# TSOC_GROVEY_ADC.net
KiCad netlist of a schematic drawn in EAGLE
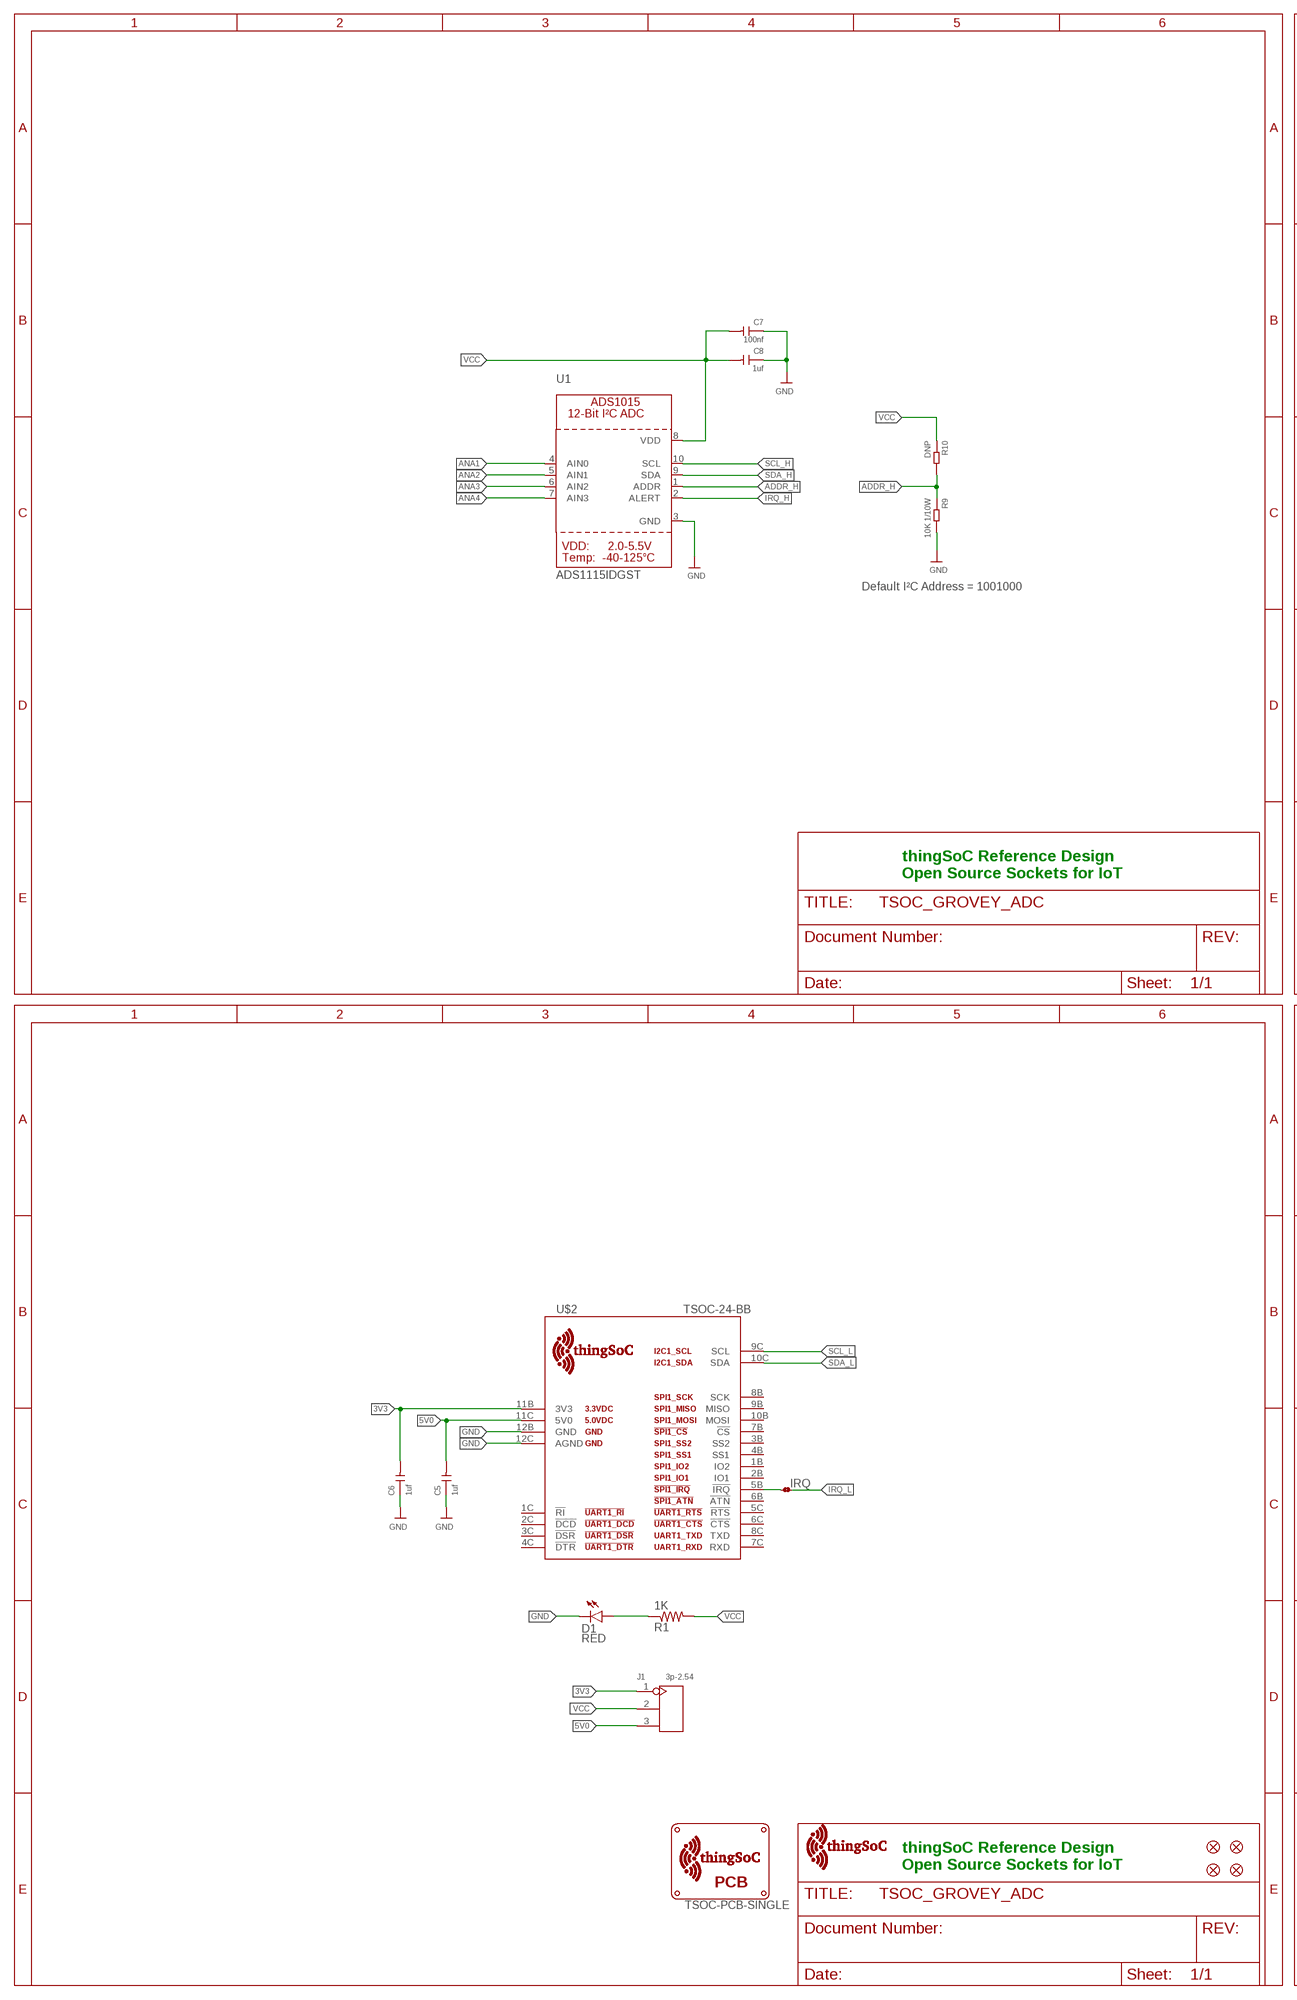
[diagram p0: schematic, sheet 1, part 1 of 2]
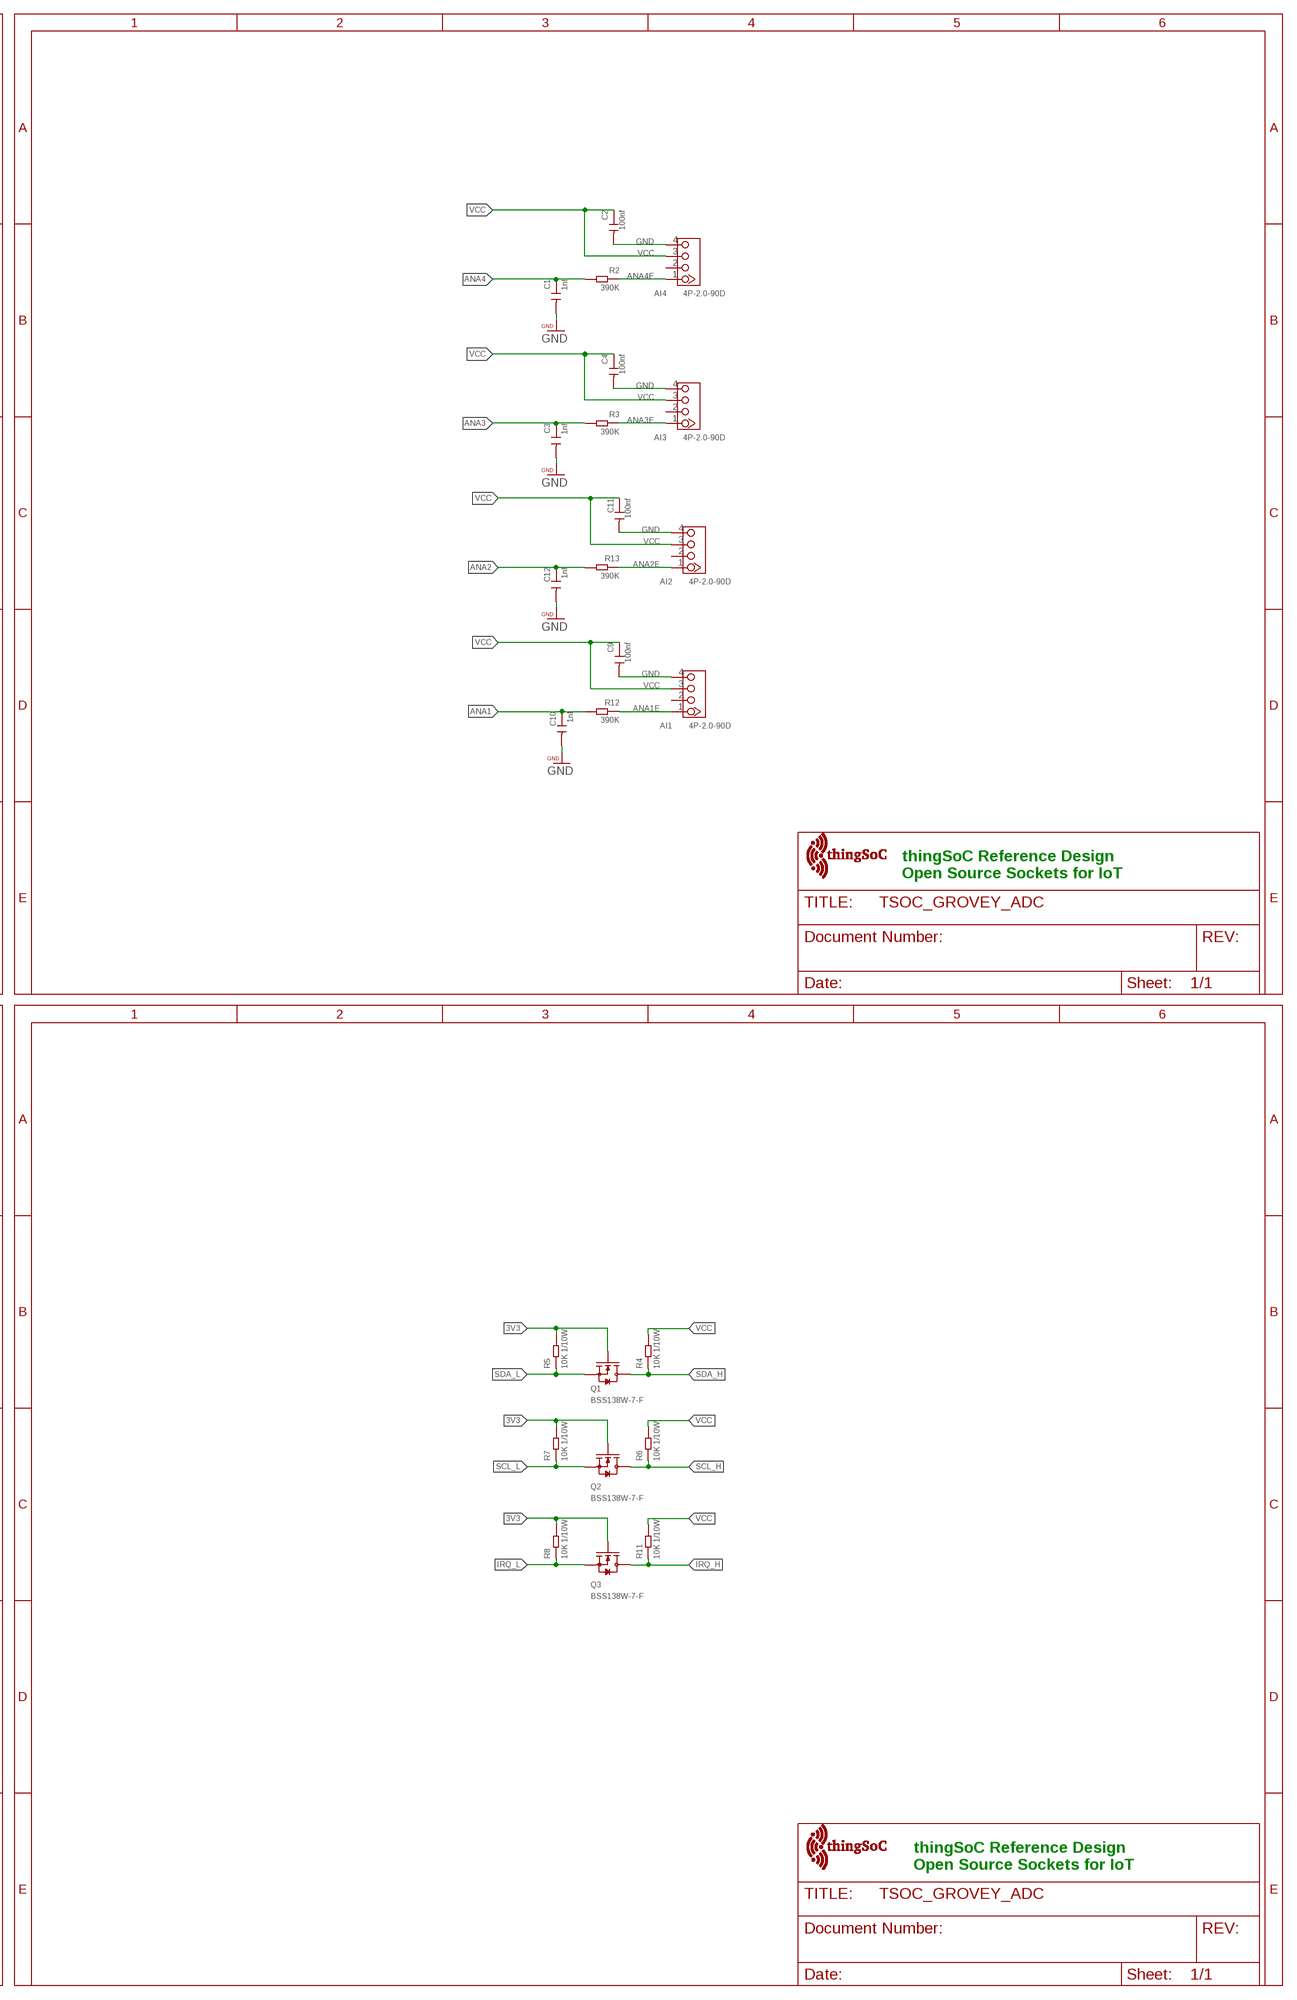
[diagram p1: schematic, sheet 1, part 2 of 2]

(export (version "E")
  (design (tool "Eeschema 10.0.6"))
  (components
    (comp (ref "AI1")
      (value "4P-2.0-90D")
      (footprint "eagle-import:HW4-2.0-90D")
      (libsource (lib "eagle-import") (part "GROVE-CONNECTOR-DIP-90D(4P-2.0)"))
    )
    (comp (ref "AI2")
      (value "4P-2.0-90D")
      (footprint "eagle-import:HW4-2.0-90D")
      (libsource (lib "eagle-import") (part "GROVE-CONNECTOR-DIP-90D(4P-2.0)"))
    )
    (comp (ref "AI3")
      (value "4P-2.0-90D")
      (footprint "eagle-import:HW4-2.0-90D")
      (libsource (lib "eagle-import") (part "GROVE-CONNECTOR-DIP-90D(4P-2.0)"))
    )
    (comp (ref "AI4")
      (value "4P-2.0-90D")
      (footprint "eagle-import:HW4-2.0-90D")
      (libsource (lib "eagle-import") (part "GROVE-CONNECTOR-DIP-90D(4P-2.0)"))
    )
    (comp (ref "C1")
      (value "1nf")
      (footprint "eagle-import:C0603")
      (fields (field (name "MPN") "GRM1885C1H102JA01D"))
      (libsource (lib "eagle-import") (part "CERAMIC-1NF-50V-5%-C0G(0603)"))
    )
    (comp (ref "C2")
      (value "100nf")
      (footprint "eagle-import:C0603")
      (fields (field (name "MPN") "CC0603KRX7R9BB104"))
      (libsource (lib "eagle-import") (part "CERAMIC-100NF-50V-10%-X7R(0603)"))
    )
    (comp (ref "C3")
      (value "1nf")
      (footprint "eagle-import:C0603")
      (fields (field (name "MPN") "GRM1885C1H102JA01D"))
      (libsource (lib "eagle-import") (part "CERAMIC-1NF-50V-5%-C0G(0603)"))
    )
    (comp (ref "C4")
      (value "100nf")
      (footprint "eagle-import:C0603")
      (fields (field (name "MPN") "CC0603KRX7R9BB104"))
      (libsource (lib "eagle-import") (part "CERAMIC-100NF-50V-10%-X7R(0603)"))
    )
    (comp (ref "C5")
      (value "1uf")
      (footprint "eagle-import:C0603")
      (fields (field (name "MPN") "CC0603KRX7R8BB105"))
      (libsource (lib "eagle-import") (part "CERAMIC-1UF-25V-10%-X7R(0603)"))
    )
    (comp (ref "C6")
      (value "1uf")
      (footprint "eagle-import:C0603")
      (fields (field (name "MPN") "CC0603KRX7R8BB105"))
      (libsource (lib "eagle-import") (part "CERAMIC-1UF-25V-10%-X7R(0603)"))
    )
    (comp (ref "C7")
      (value "100nf")
      (footprint "eagle-import:C0603")
      (fields (field (name "MPN") "CC0603KRX7R9BB104"))
      (libsource (lib "eagle-import") (part "CERAMIC-100NF-50V-10%-X7R(0603)"))
    )
    (comp (ref "C8")
      (value "1uf")
      (footprint "eagle-import:C0603")
      (fields (field (name "MPN") "CC0603KRX7R8BB105"))
      (libsource (lib "eagle-import") (part "CERAMIC-1UF-25V-10%-X7R(0603)"))
    )
    (comp (ref "C9")
      (value "100nf")
      (footprint "eagle-import:C0603")
      (fields (field (name "MPN") "CC0603KRX7R9BB104"))
      (libsource (lib "eagle-import") (part "CERAMIC-100NF-50V-10%-X7R(0603)"))
    )
    (comp (ref "C10")
      (value "1nf")
      (footprint "eagle-import:C0603")
      (fields (field (name "MPN") "GRM1885C1H102JA01D"))
      (libsource (lib "eagle-import") (part "CERAMIC-1NF-50V-5%-C0G(0603)"))
    )
    (comp (ref "C11")
      (value "100nf")
      (footprint "eagle-import:C0603")
      (fields (field (name "MPN") "CC0603KRX7R9BB104"))
      (libsource (lib "eagle-import") (part "CERAMIC-100NF-50V-10%-X7R(0603)"))
    )
    (comp (ref "C12")
      (value "1nf")
      (footprint "eagle-import:C0603")
      (fields (field (name "MPN") "GRM1885C1H102JA01D"))
      (libsource (lib "eagle-import") (part "CERAMIC-1NF-50V-5%-C0G(0603)"))
    )
    (comp (ref "D1")
      (value "RED")
      (footprint "eagle-import:LED-0603")
      (libsource (lib "eagle-import") (part "LED0603"))
    )
    (comp (ref "FID1")
      (value "FIDUCIALUFIDUCIAL")
      (footprint "eagle-import:MICRO-FIDUCIAL")
      (libsource (lib "eagle-import") (part "FIDUCIALUFIDUCIAL"))
    )
    (comp (ref "FID2")
      (value "FIDUCIALUFIDUCIAL")
      (footprint "eagle-import:MICRO-FIDUCIAL")
      (libsource (lib "eagle-import") (part "FIDUCIALUFIDUCIAL"))
    )
    (comp (ref "FID3")
      (value "FIDUCIALUFIDUCIAL")
      (footprint "eagle-import:MICRO-FIDUCIAL")
      (libsource (lib "eagle-import") (part "FIDUCIALUFIDUCIAL"))
    )
    (comp (ref "FID4")
      (value "FIDUCIALUFIDUCIAL")
      (footprint "eagle-import:MICRO-FIDUCIAL")
      (libsource (lib "eagle-import") (part "FIDUCIALUFIDUCIAL"))
    )
    (comp (ref "IRQ")
      (value "JMP-2-NO")
      (footprint "eagle-import:JMP-2-NO")
      (libsource (lib "eagle-import") (part "JMP-2-NO"))
    )
    (comp (ref "J1")
      (value "3p-2.54")
      (footprint "eagle-import:H3-2.54")
      (libsource (lib "eagle-import") (part "DIP-BLACK-MALE-HEADER-VERT(3P-2.54)"))
    )
    (comp (ref "Q1")
      (value "BSS138W-7-F")
      (footprint "eagle-import:SOT-23")
      (libsource (lib "eagle-import") (part "SMD-MOSFET-N-CH-50V-200MA-BSS138W-7-F(SOT-23)"))
    )
    (comp (ref "Q2")
      (value "BSS138W-7-F")
      (footprint "eagle-import:SOT-23")
      (libsource (lib "eagle-import") (part "SMD-MOSFET-N-CH-50V-200MA-BSS138W-7-F(SOT-23)"))
    )
    (comp (ref "Q3")
      (value "BSS138W-7-F")
      (footprint "eagle-import:SOT-23")
      (libsource (lib "eagle-import") (part "SMD-MOSFET-N-CH-50V-200MA-BSS138W-7-F(SOT-23)"))
    )
    (comp (ref "R1")
      (value "1K")
      (footprint "eagle-import:0603-RES")
      (libsource (lib "eagle-import") (part "RESISTOR_SFE0603-RES"))
    )
    (comp (ref "R2")
      (value "390K")
      (footprint "eagle-import:R0603")
      (fields (field (name "MPN") "RC0603FR-07150KL"))
      (libsource (lib "eagle-import") (part "SMD-RES-150K-1%-1/10W(0603)"))
    )
    (comp (ref "R3")
      (value "390K")
      (footprint "eagle-import:R0603")
      (fields (field (name "MPN") "RC0603FR-07150KL"))
      (libsource (lib "eagle-import") (part "SMD-RES-150K-1%-1/10W(0603)"))
    )
    (comp (ref "R4")
      (value "10K 1/10W")
      (footprint "eagle-import:R0603")
      (fields (field (name "MPN") "RC0603JR-0710KL"))
      (libsource (lib "eagle-import") (part "SMD-RES-10K-5%-1/10W(0603)"))
    )
    (comp (ref "R5")
      (value "10K 1/10W")
      (footprint "eagle-import:R0603")
      (fields (field (name "MPN") "RC0603JR-0710KL"))
      (libsource (lib "eagle-import") (part "SMD-RES-10K-5%-1/10W(0603)"))
    )
    (comp (ref "R6")
      (value "10K 1/10W")
      (footprint "eagle-import:R0603")
      (fields (field (name "MPN") "RC0603JR-0710KL"))
      (libsource (lib "eagle-import") (part "SMD-RES-10K-5%-1/10W(0603)"))
    )
    (comp (ref "R7")
      (value "10K 1/10W")
      (footprint "eagle-import:R0603")
      (fields (field (name "MPN") "RC0603JR-0710KL"))
      (libsource (lib "eagle-import") (part "SMD-RES-10K-5%-1/10W(0603)"))
    )
    (comp (ref "R8")
      (value "10K 1/10W")
      (footprint "eagle-import:R0603")
      (fields (field (name "MPN") "RC0603JR-0710KL"))
      (libsource (lib "eagle-import") (part "SMD-RES-10K-5%-1/10W(0603)"))
    )
    (comp (ref "R9")
      (value "10K 1/10W")
      (footprint "eagle-import:R0603")
      (fields (field (name "MPN") "RC0603JR-0710KL"))
      (libsource (lib "eagle-import") (part "SMD-RES-10K-5%-1/10W(0603)"))
    )
    (comp (ref "R10")
      (value "DNP")
      (footprint "eagle-import:R0603")
      (fields (field (name "MPN") "RC0603JR-0710KL"))
      (libsource (lib "eagle-import") (part "SMD-RES-10K-5%-1/10W(0603)"))
    )
    (comp (ref "R11")
      (value "10K 1/10W")
      (footprint "eagle-import:R0603")
      (fields (field (name "MPN") "RC0603JR-0710KL"))
      (libsource (lib "eagle-import") (part "SMD-RES-10K-5%-1/10W(0603)"))
    )
    (comp (ref "R12")
      (value "390K")
      (footprint "eagle-import:R0603")
      (fields (field (name "MPN") "RC0603FR-07150KL"))
      (libsource (lib "eagle-import") (part "SMD-RES-150K-1%-1/10W(0603)"))
    )
    (comp (ref "R13")
      (value "390K")
      (footprint "eagle-import:R0603")
      (fields (field (name "MPN") "RC0603FR-07150KL"))
      (libsource (lib "eagle-import") (part "SMD-RES-150K-1%-1/10W(0603)"))
    )
    (comp (ref "U$1")
      (value "TSOC-PCB-SINGLE")
      (footprint "eagle-import:TSOC-BB-BRD-DIM")
      (libsource (lib "eagle-import") (part "TSOC-PCB-SINGLE"))
    )
    (comp (ref "U$2")
      (value "TSOC-24-BB")
      (footprint "eagle-import:TSOC-BB-S24")
      (libsource (lib "eagle-import") (part "TSOC-24-BB"))
    )
    (comp (ref "U$100")
      (value "TSOC-LOGO-SMALL")
      (footprint "eagle-import:TSOC-LOGO-SML")
      (libsource (lib "eagle-import") (part "TSOC-LOGO-SMALL"))
    )
    (comp (ref "U$102")
      (value "TSOC-LOGO-LRG")
      (footprint "eagle-import:TSOC-LOGO-LRG")
      (libsource (lib "eagle-import") (part "TSOC-LOGO-LRG"))
    )
    (comp (ref "U$103")
      (value "TSOC-LOGO-SMALL")
      (footprint "eagle-import:TSOC-LOGO-SML")
      (libsource (lib "eagle-import") (part "TSOC-LOGO-SMALL"))
    )
    (comp (ref "U1")
      (value "ADS1115IDGST")
      (footprint "eagle-import:MSOP10")
      (libsource (lib "eagle-import") (part "ADC_ADS1015"))
    )
  )
  (nets
    (net (code "1") (name "/ANA1E") (class "Default")
      (node (ref "AI1") (pin "1") (pinfunction "1_1") (pintype "bidirectional"))
      (node (ref "R12") (pin "1") (pinfunction "1_1") (pintype "passive"))
    )
    (net (code "2") (name "/ANA2E") (class "Default")
      (node (ref "AI2") (pin "1") (pinfunction "1_1") (pintype "bidirectional"))
      (node (ref "R13") (pin "1") (pinfunction "1_1") (pintype "passive"))
    )
    (net (code "3") (name "/ANA3E") (class "Default")
      (node (ref "AI3") (pin "1") (pinfunction "1_1") (pintype "bidirectional"))
      (node (ref "R3") (pin "1") (pinfunction "1_1") (pintype "passive"))
    )
    (net (code "4") (name "/ANA4E") (class "Default")
      (node (ref "AI4") (pin "1") (pinfunction "1_1") (pintype "bidirectional"))
      (node (ref "R2") (pin "1") (pinfunction "1_1") (pintype "passive"))
    )
    (net (code "5") (name "3V3") (class "Default")
      (node (ref "C6") (pin "2") (pinfunction "2_2") (pintype "passive"))
      (node (ref "J1") (pin "1") (pinfunction "P$1_1") (pintype "bidirectional"))
      (node (ref "Q1") (pin "1") (pinfunction "G_1") (pintype "passive"))
      (node (ref "Q2") (pin "1") (pinfunction "G_1") (pintype "passive"))
      (node (ref "Q3") (pin "1") (pinfunction "G_1") (pintype "passive"))
      (node (ref "R5") (pin "2") (pinfunction "2_2") (pintype "passive"))
      (node (ref "R7") (pin "2") (pinfunction "2_2") (pintype "passive"))
      (node (ref "R8") (pin "2") (pinfunction "2_2") (pintype "passive"))
      (node (ref "U$2") (pin "11B") (pinfunction "3V3_11B") (pintype "bidirectional"))
    )
    (net (code "6") (name "5V0") (class "Default")
      (node (ref "C5") (pin "2") (pinfunction "2_2") (pintype "passive"))
      (node (ref "J1") (pin "3") (pinfunction "P$3_3") (pintype "bidirectional"))
      (node (ref "U$2") (pin "11C") (pinfunction "5V0_11C") (pintype "bidirectional"))
    )
    (net (code "7") (name "ADDR_H") (class "Default")
      (node (ref "R10") (pin "2") (pinfunction "2_2") (pintype "passive"))
      (node (ref "R9") (pin "1") (pinfunction "1_1") (pintype "passive"))
      (node (ref "U1") (pin "1") (pinfunction "ADDR_1") (pintype "bidirectional"))
    )
    (net (code "8") (name "ANA1") (class "Default")
      (node (ref "C10") (pin "1") (pinfunction "1_1") (pintype "passive"))
      (node (ref "R12") (pin "2") (pinfunction "2_2") (pintype "passive"))
      (node (ref "U1") (pin "4") (pinfunction "AIN0_4") (pintype "bidirectional"))
    )
    (net (code "9") (name "ANA2") (class "Default")
      (node (ref "C12") (pin "1") (pinfunction "1_1") (pintype "passive"))
      (node (ref "R13") (pin "2") (pinfunction "2_2") (pintype "passive"))
      (node (ref "U1") (pin "5") (pinfunction "AIN1_5") (pintype "bidirectional"))
    )
    (net (code "10") (name "ANA3") (class "Default")
      (node (ref "C3") (pin "1") (pinfunction "1_1") (pintype "passive"))
      (node (ref "R3") (pin "2") (pinfunction "2_2") (pintype "passive"))
      (node (ref "U1") (pin "6") (pinfunction "AIN2_6") (pintype "bidirectional"))
    )
    (net (code "11") (name "ANA4") (class "Default")
      (node (ref "C1") (pin "1") (pinfunction "1_1") (pintype "passive"))
      (node (ref "R2") (pin "2") (pinfunction "2_2") (pintype "passive"))
      (node (ref "U1") (pin "7") (pinfunction "AIN3_7") (pintype "bidirectional"))
    )
    (net (code "12") (name "GND") (class "Default")
      (node (ref "AI1") (pin "4") (pinfunction "4_4") (pintype "bidirectional"))
      (node (ref "AI2") (pin "4") (pinfunction "4_4") (pintype "bidirectional"))
      (node (ref "AI3") (pin "4") (pinfunction "4_4") (pintype "bidirectional"))
      (node (ref "AI4") (pin "4") (pinfunction "4_4") (pintype "bidirectional"))
      (node (ref "C1") (pin "2") (pinfunction "2_2") (pintype "passive"))
      (node (ref "C10") (pin "2") (pinfunction "2_2") (pintype "passive"))
      (node (ref "C11") (pin "2") (pinfunction "2_2") (pintype "passive"))
      (node (ref "C12") (pin "2") (pinfunction "2_2") (pintype "passive"))
      (node (ref "C2") (pin "2") (pinfunction "2_2") (pintype "passive"))
      (node (ref "C3") (pin "2") (pinfunction "2_2") (pintype "passive"))
      (node (ref "C4") (pin "2") (pinfunction "2_2") (pintype "passive"))
      (node (ref "C5") (pin "1") (pinfunction "1_1") (pintype "passive"))
      (node (ref "C6") (pin "1") (pinfunction "1_1") (pintype "passive"))
      (node (ref "C7") (pin "1") (pinfunction "1_1") (pintype "passive"))
      (node (ref "C8") (pin "1") (pinfunction "1_1") (pintype "passive"))
      (node (ref "C9") (pin "2") (pinfunction "2_2") (pintype "passive"))
      (node (ref "D1") (pin "C") (pinfunction "C_C") (pintype "passive"))
      (node (ref "R9") (pin "2") (pinfunction "2_2") (pintype "passive"))
      (node (ref "U$2") (pin "12B") (pinfunction "GND_12B") (pintype "bidirectional"))
      (node (ref "U$2") (pin "12C") (pinfunction "AGND_12C") (pintype "bidirectional"))
      (node (ref "U1") (pin "3") (pinfunction "GND_3") (pintype "bidirectional"))
    )
    (net (code "13") (name "IRQ_H") (class "Default")
      (node (ref "Q3") (pin "3") (pinfunction "D_3") (pintype "passive"))
      (node (ref "R11") (pin "1") (pinfunction "1_1") (pintype "passive"))
      (node (ref "U1") (pin "2") (pinfunction "ALERT_2") (pintype "bidirectional"))
    )
    (net (code "14") (name "IRQ_L") (class "Default")
      (node (ref "IRQ") (pin "2") (pinfunction "2_2") (pintype "passive"))
      (node (ref "Q3") (pin "2") (pinfunction "S_2") (pintype "passive"))
      (node (ref "R8") (pin "1") (pinfunction "1_1") (pintype "passive"))
    )
    (net (code "15") (name "Net-(D1-PadA)") (class "Default")
      (node (ref "D1") (pin "A") (pinfunction "A_A") (pintype "passive"))
      (node (ref "R1") (pin "1") (pinfunction "1_1") (pintype "passive"))
    )
    (net (code "16") (name "Net-(U$2-~{IRQ})") (class "Default")
      (node (ref "IRQ") (pin "1") (pinfunction "1_1") (pintype "passive"))
      (node (ref "U$2") (pin "5B") (pinfunction "~{IRQ}_5B") (pintype "bidirectional"))
    )
    (net (code "17") (name "SCL_H") (class "Default")
      (node (ref "Q2") (pin "3") (pinfunction "D_3") (pintype "passive"))
      (node (ref "R6") (pin "1") (pinfunction "1_1") (pintype "passive"))
      (node (ref "U1") (pin "10") (pinfunction "SCL_10") (pintype "bidirectional"))
    )
    (net (code "18") (name "SCL_L") (class "Default")
      (node (ref "Q2") (pin "2") (pinfunction "S_2") (pintype "passive"))
      (node (ref "R7") (pin "1") (pinfunction "1_1") (pintype "passive"))
      (node (ref "U$2") (pin "9C") (pinfunction "SCL_9C") (pintype "bidirectional"))
    )
    (net (code "19") (name "SDA_H") (class "Default")
      (node (ref "Q1") (pin "3") (pinfunction "D_3") (pintype "passive"))
      (node (ref "R4") (pin "1") (pinfunction "1_1") (pintype "passive"))
      (node (ref "U1") (pin "9") (pinfunction "SDA_9") (pintype "bidirectional"))
    )
    (net (code "20") (name "SDA_L") (class "Default")
      (node (ref "Q1") (pin "2") (pinfunction "S_2") (pintype "passive"))
      (node (ref "R5") (pin "1") (pinfunction "1_1") (pintype "passive"))
      (node (ref "U$2") (pin "10C") (pinfunction "SDA_10C") (pintype "bidirectional"))
    )
    (net (code "21") (name "VCC") (class "Default")
      (node (ref "AI1") (pin "3") (pinfunction "3_3") (pintype "bidirectional"))
      (node (ref "AI2") (pin "3") (pinfunction "3_3") (pintype "bidirectional"))
      (node (ref "AI3") (pin "3") (pinfunction "3_3") (pintype "bidirectional"))
      (node (ref "AI4") (pin "3") (pinfunction "3_3") (pintype "bidirectional"))
      (node (ref "C11") (pin "1") (pinfunction "1_1") (pintype "passive"))
      (node (ref "C2") (pin "1") (pinfunction "1_1") (pintype "passive"))
      (node (ref "C4") (pin "1") (pinfunction "1_1") (pintype "passive"))
      (node (ref "C7") (pin "2") (pinfunction "2_2") (pintype "passive"))
      (node (ref "C8") (pin "2") (pinfunction "2_2") (pintype "passive"))
      (node (ref "C9") (pin "1") (pinfunction "1_1") (pintype "passive"))
      (node (ref "J1") (pin "2") (pinfunction "P$2_2") (pintype "bidirectional"))
      (node (ref "R1") (pin "2") (pinfunction "2_2") (pintype "passive"))
      (node (ref "R10") (pin "1") (pinfunction "1_1") (pintype "passive"))
      (node (ref "R11") (pin "2") (pinfunction "2_2") (pintype "passive"))
      (node (ref "R4") (pin "2") (pinfunction "2_2") (pintype "passive"))
      (node (ref "R6") (pin "2") (pinfunction "2_2") (pintype "passive"))
      (node (ref "U1") (pin "8") (pinfunction "VDD_8") (pintype "bidirectional"))
    )
    (net (code "22") (name "unconnected-(AI1-Pad2)") (class "Default")
      (node (ref "AI1") (pin "2") (pinfunction "2_2") (pintype "bidirectional"))
    )
    (net (code "23") (name "unconnected-(AI2-Pad2)") (class "Default")
      (node (ref "AI2") (pin "2") (pinfunction "2_2") (pintype "bidirectional"))
    )
    (net (code "24") (name "unconnected-(AI3-Pad2)") (class "Default")
      (node (ref "AI3") (pin "2") (pinfunction "2_2") (pintype "bidirectional"))
    )
    (net (code "25") (name "unconnected-(AI4-Pad2)") (class "Default")
      (node (ref "AI4") (pin "2") (pinfunction "2_2") (pintype "bidirectional"))
    )
    (net (code "26") (name "unconnected-(U$2-IO1-Pad2B)") (class "Default")
      (node (ref "U$2") (pin "2B") (pinfunction "IO1_2B") (pintype "bidirectional"))
    )
    (net (code "27") (name "unconnected-(U$2-IO2-Pad1B)") (class "Default")
      (node (ref "U$2") (pin "1B") (pinfunction "IO2_1B") (pintype "bidirectional"))
    )
    (net (code "28") (name "unconnected-(U$2-MISO-Pad9B)") (class "Default")
      (node (ref "U$2") (pin "9B") (pinfunction "MISO_9B") (pintype "bidirectional"))
    )
    (net (code "29") (name "unconnected-(U$2-MOSI-Pad10B)") (class "Default")
      (node (ref "U$2") (pin "10B") (pinfunction "MOSI_10B") (pintype "bidirectional"))
    )
    (net (code "30") (name "unconnected-(U$2-RXD-Pad7C)") (class "Default")
      (node (ref "U$2") (pin "7C") (pinfunction "RXD_7C") (pintype "bidirectional"))
    )
    (net (code "31") (name "unconnected-(U$2-SCK-Pad8B)") (class "Default")
      (node (ref "U$2") (pin "8B") (pinfunction "SCK_8B") (pintype "bidirectional"))
    )
    (net (code "32") (name "unconnected-(U$2-SS1-Pad4B)") (class "Default")
      (node (ref "U$2") (pin "4B") (pinfunction "SS1_4B") (pintype "bidirectional"))
    )
    (net (code "33") (name "unconnected-(U$2-SS2-Pad3B)") (class "Default")
      (node (ref "U$2") (pin "3B") (pinfunction "SS2_3B") (pintype "bidirectional"))
    )
    (net (code "34") (name "unconnected-(U$2-TXD-Pad8C)") (class "Default")
      (node (ref "U$2") (pin "8C") (pinfunction "TXD_8C") (pintype "bidirectional"))
    )
    (net (code "35") (name "unconnected-(U$2-~{ATN}-Pad6B)") (class "Default")
      (node (ref "U$2") (pin "6B") (pinfunction "~{ATN}_6B") (pintype "bidirectional"))
    )
    (net (code "36") (name "unconnected-(U$2-~{CS}-Pad7B)") (class "Default")
      (node (ref "U$2") (pin "7B") (pinfunction "~{CS}_7B") (pintype "bidirectional"))
    )
    (net (code "37") (name "unconnected-(U$2-~{CTS}-Pad6C)") (class "Default")
      (node (ref "U$2") (pin "6C") (pinfunction "~{CTS}_6C") (pintype "bidirectional"))
    )
    (net (code "38") (name "unconnected-(U$2-~{DCD}-Pad2C)") (class "Default")
      (node (ref "U$2") (pin "2C") (pinfunction "~{DCD}_2C") (pintype "bidirectional"))
    )
    (net (code "39") (name "unconnected-(U$2-~{DSR}-Pad3C)") (class "Default")
      (node (ref "U$2") (pin "3C") (pinfunction "~{DSR}_3C") (pintype "bidirectional"))
    )
    (net (code "40") (name "unconnected-(U$2-~{DTR}-Pad4C)") (class "Default")
      (node (ref "U$2") (pin "4C") (pinfunction "~{DTR}_4C") (pintype "bidirectional"))
    )
    (net (code "41") (name "unconnected-(U$2-~{RI}-Pad1C)") (class "Default")
      (node (ref "U$2") (pin "1C") (pinfunction "~{RI}_1C") (pintype "bidirectional"))
    )
    (net (code "42") (name "unconnected-(U$2-~{RTS}-Pad5C)") (class "Default")
      (node (ref "U$2") (pin "5C") (pinfunction "~{RTS}_5C") (pintype "bidirectional"))
    )
  )
)
